# 505153_1_1.net
KiCad netlist of a schematic drawn in Altium Designer
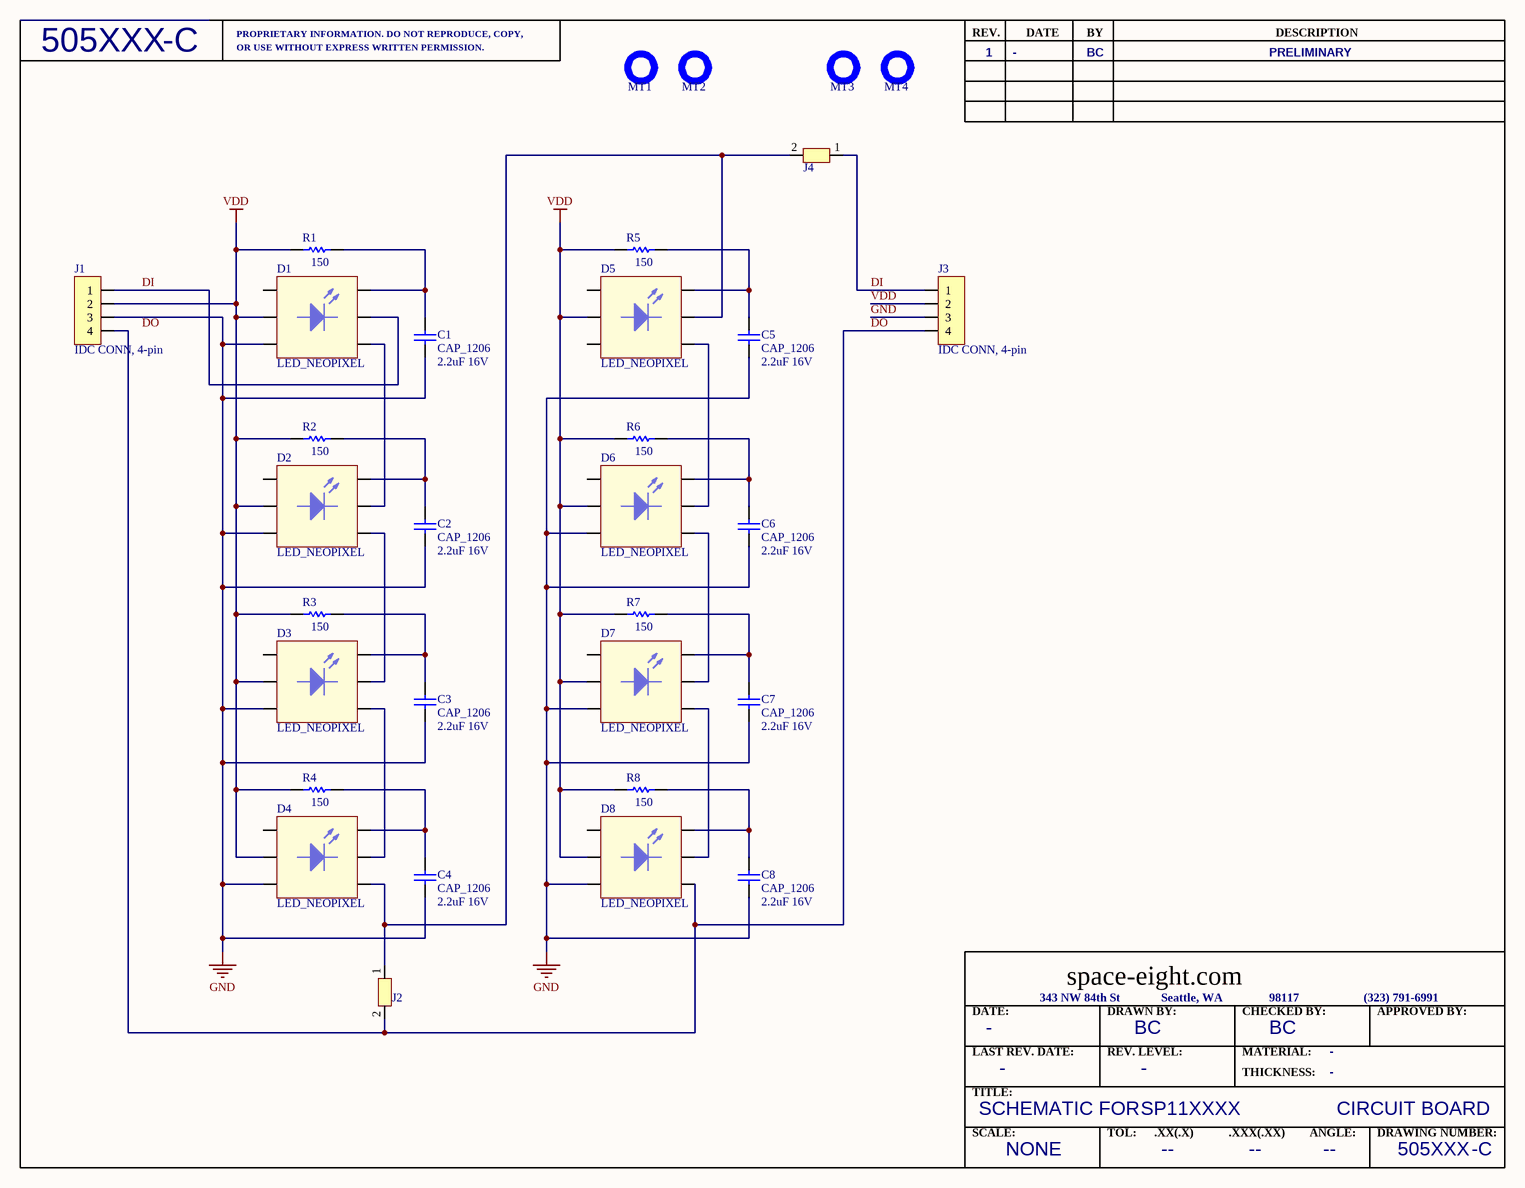
[diagram p0: 505153_1_1.SchDoc]

(export (version "E")
  (design (tool "Eeschema 10.0.6"))
  (components
    (comp (ref "C1")
      (value "CAP_1206")
      (footprint "SMT_1206_MOD")
      (description "CAP")
      (fields
        (field (name "MANUFACTURER") "Generic Components")
        (field (name "ALTIUM_VALUE") "2.2uF 16V")
        (field (name "PUBLISHER") "Altium Limited")
      )
      (libsource (lib "Custom_Lib_2") (part "CAP_1206"))
    )
    (comp (ref "C2")
      (value "CAP_1206")
      (footprint "SMT_1206_MOD")
      (description "CAP")
      (fields
        (field (name "MANUFACTURER") "Generic Components")
        (field (name "ALTIUM_VALUE") "2.2uF 16V")
        (field (name "PUBLISHER") "Altium Limited")
      )
      (libsource (lib "Custom_Lib_2") (part "CAP_1206"))
    )
    (comp (ref "C3")
      (value "CAP_1206")
      (footprint "SMT_1206_MOD")
      (description "CAP")
      (fields
        (field (name "MANUFACTURER") "Generic Components")
        (field (name "ALTIUM_VALUE") "2.2uF 16V")
        (field (name "PUBLISHER") "Altium Limited")
      )
      (libsource (lib "Custom_Lib_2") (part "CAP_1206"))
    )
    (comp (ref "C4")
      (value "CAP_1206")
      (footprint "SMT_1206_MOD")
      (description "CAP")
      (fields
        (field (name "MANUFACTURER") "Generic Components")
        (field (name "ALTIUM_VALUE") "2.2uF 16V")
        (field (name "PUBLISHER") "Altium Limited")
      )
      (libsource (lib "Custom_Lib_2") (part "CAP_1206"))
    )
    (comp (ref "C5")
      (value "CAP_1206")
      (footprint "SMT_1206_MOD")
      (description "CAP")
      (fields
        (field (name "MANUFACTURER") "Generic Components")
        (field (name "ALTIUM_VALUE") "2.2uF 16V")
        (field (name "PUBLISHER") "Altium Limited")
      )
      (libsource (lib "Custom_Lib_2") (part "CAP_1206"))
    )
    (comp (ref "C6")
      (value "CAP_1206")
      (footprint "SMT_1206_MOD")
      (description "CAP")
      (fields
        (field (name "MANUFACTURER") "Generic Components")
        (field (name "ALTIUM_VALUE") "2.2uF 16V")
        (field (name "PUBLISHER") "Altium Limited")
      )
      (libsource (lib "Custom_Lib_2") (part "CAP_1206"))
    )
    (comp (ref "C7")
      (value "CAP_1206")
      (footprint "SMT_1206_MOD")
      (description "CAP")
      (fields
        (field (name "MANUFACTURER") "Generic Components")
        (field (name "ALTIUM_VALUE") "2.2uF 16V")
        (field (name "PUBLISHER") "Altium Limited")
      )
      (libsource (lib "Custom_Lib_2") (part "CAP_1206"))
    )
    (comp (ref "C8")
      (value "CAP_1206")
      (footprint "SMT_1206_MOD")
      (description "CAP")
      (fields
        (field (name "MANUFACTURER") "Generic Components")
        (field (name "ALTIUM_VALUE") "2.2uF 16V")
        (field (name "PUBLISHER") "Altium Limited")
      )
      (libsource (lib "Custom_Lib_2") (part "CAP_1206"))
    )
    (comp (ref "D1")
      (value "LED_NEOPIXEL")
      (footprint "NEOPIXEL")
      (description "RGB NEOPIXEL")
      (fields (field (name "MANUFACTURER") "Generic Components") (field (name "PUBLISHER") "Altium Limited"))
      (libsource (lib "Custom_Lib_2") (part "LED_NEOPIXEL"))
    )
    (comp (ref "D2")
      (value "LED_NEOPIXEL")
      (footprint "NEOPIXEL")
      (description "RGB NEOPIXEL")
      (fields (field (name "MANUFACTURER") "Generic Components") (field (name "PUBLISHER") "Altium Limited"))
      (libsource (lib "Custom_Lib_2") (part "LED_NEOPIXEL"))
    )
    (comp (ref "D3")
      (value "LED_NEOPIXEL")
      (footprint "NEOPIXEL")
      (description "RGB NEOPIXEL")
      (fields (field (name "MANUFACTURER") "Generic Components") (field (name "PUBLISHER") "Altium Limited"))
      (libsource (lib "Custom_Lib_2") (part "LED_NEOPIXEL"))
    )
    (comp (ref "D4")
      (value "LED_NEOPIXEL")
      (footprint "NEOPIXEL")
      (description "RGB NEOPIXEL")
      (fields (field (name "MANUFACTURER") "Generic Components") (field (name "PUBLISHER") "Altium Limited"))
      (libsource (lib "Custom_Lib_2") (part "LED_NEOPIXEL"))
    )
    (comp (ref "D5")
      (value "LED_NEOPIXEL")
      (footprint "NEOPIXEL")
      (description "RGB NEOPIXEL")
      (fields (field (name "MANUFACTURER") "Generic Components") (field (name "PUBLISHER") "Altium Limited"))
      (libsource (lib "Custom_Lib_2") (part "LED_NEOPIXEL"))
    )
    (comp (ref "D6")
      (value "LED_NEOPIXEL")
      (footprint "NEOPIXEL")
      (description "RGB NEOPIXEL")
      (fields (field (name "MANUFACTURER") "Generic Components") (field (name "PUBLISHER") "Altium Limited"))
      (libsource (lib "Custom_Lib_2") (part "LED_NEOPIXEL"))
    )
    (comp (ref "D7")
      (value "LED_NEOPIXEL")
      (footprint "NEOPIXEL")
      (description "RGB NEOPIXEL")
      (fields (field (name "MANUFACTURER") "Generic Components") (field (name "PUBLISHER") "Altium Limited"))
      (libsource (lib "Custom_Lib_2") (part "LED_NEOPIXEL"))
    )
    (comp (ref "D8")
      (value "LED_NEOPIXEL")
      (footprint "NEOPIXEL")
      (description "RGB NEOPIXEL")
      (fields (field (name "MANUFACTURER") "Generic Components") (field (name "PUBLISHER") "Altium Limited"))
      (libsource (lib "Custom_Lib_2") (part "LED_NEOPIXEL"))
    )
    (comp (ref "J1")
      (value "IDC CONN, 4-pin")
      (footprint "IDC_CONN_SMT_4-PIN")
      (description "ICD Connector, 4-Pin")
      (fields (field (name "PUBLISHER") "Altium Limited"))
      (libsource (lib "") (part "IDC CONN, 4-pin_1"))
    )
    (comp (ref "J2") (value "JUMPER_MOD") (footprint "JUMPER_SMT") (libsource (lib "") (part "JUMPER_MOD_1")))
    (comp (ref "J3")
      (value "IDC CONN, 4-pin")
      (footprint "IDC_CONN_SMT_4-PIN")
      (description "ICD Connector, 4-Pin")
      (fields (field (name "PUBLISHER") "Altium Limited"))
      (libsource (lib "Custom_Lib_2") (part "IDC CONN, 4-pin"))
    )
    (comp (ref "J4")
      (value "JUMPER_MOD")
      (footprint "JUMPER_SMT")
      (libsource (lib "Custom_Lib_2") (part "JUMPER_MOD"))
    )
    (comp (ref "MT1")
      (value "MOUNTING HOLE")
      (footprint "MOUNTING HOLE")
      (libsource (lib "Custom_Lib_2") (part "MOUNTING HOLE"))
    )
    (comp (ref "MT2")
      (value "MOUNTING HOLE")
      (footprint "MOUNTING HOLE")
      (libsource (lib "Custom_Lib_2") (part "MOUNTING HOLE"))
    )
    (comp (ref "MT3")
      (value "MOUNTING HOLE")
      (footprint "MOUNTING HOLE")
      (libsource (lib "Custom_Lib_2") (part "MOUNTING HOLE"))
    )
    (comp (ref "MT4")
      (value "MOUNTING HOLE")
      (footprint "MOUNTING HOLE")
      (libsource (lib "Custom_Lib_2") (part "MOUNTING HOLE"))
    )
    (comp (ref "R1")
      (value "150")
      (footprint "SMT_1206_MOD")
      (description "RES")
      (fields
        (field (name "MANUFACTURER") "Generic Components")
        (field (name "Comment") "RES_1206")
        (field (name "PUBLISHER") "Altium Limited")
      )
      (libsource (lib "Custom_Lib_2") (part "RES_1206"))
    )
    (comp (ref "R2")
      (value "150")
      (footprint "SMT_1206_MOD")
      (description "RES")
      (fields
        (field (name "MANUFACTURER") "Generic Components")
        (field (name "Comment") "RES_1206")
        (field (name "PUBLISHER") "Altium Limited")
      )
      (libsource (lib "Custom_Lib_2") (part "RES_1206"))
    )
    (comp (ref "R3")
      (value "150")
      (footprint "SMT_1206_MOD")
      (description "RES")
      (fields
        (field (name "MANUFACTURER") "Generic Components")
        (field (name "Comment") "RES_1206")
        (field (name "PUBLISHER") "Altium Limited")
      )
      (libsource (lib "Custom_Lib_2") (part "RES_1206"))
    )
    (comp (ref "R4")
      (value "150")
      (footprint "SMT_1206_MOD")
      (description "RES")
      (fields
        (field (name "MANUFACTURER") "Generic Components")
        (field (name "Comment") "RES_1206")
        (field (name "PUBLISHER") "Altium Limited")
      )
      (libsource (lib "Custom_Lib_2") (part "RES_1206"))
    )
    (comp (ref "R5")
      (value "150")
      (footprint "SMT_1206_MOD")
      (description "RES")
      (fields
        (field (name "MANUFACTURER") "Generic Components")
        (field (name "Comment") "RES_1206")
        (field (name "PUBLISHER") "Altium Limited")
      )
      (libsource (lib "Custom_Lib_2") (part "RES_1206"))
    )
    (comp (ref "R6")
      (value "150")
      (footprint "SMT_1206_MOD")
      (description "RES")
      (fields
        (field (name "MANUFACTURER") "Generic Components")
        (field (name "Comment") "RES_1206")
        (field (name "PUBLISHER") "Altium Limited")
      )
      (libsource (lib "Custom_Lib_2") (part "RES_1206"))
    )
    (comp (ref "R7")
      (value "150")
      (footprint "SMT_1206_MOD")
      (description "RES")
      (fields
        (field (name "MANUFACTURER") "Generic Components")
        (field (name "Comment") "RES_1206")
        (field (name "PUBLISHER") "Altium Limited")
      )
      (libsource (lib "Custom_Lib_2") (part "RES_1206"))
    )
    (comp (ref "R8")
      (value "150")
      (footprint "SMT_1206_MOD")
      (description "RES")
      (fields
        (field (name "MANUFACTURER") "Generic Components")
        (field (name "Comment") "RES_1206")
        (field (name "PUBLISHER") "Altium Limited")
      )
      (libsource (lib "Custom_Lib_2") (part "RES_1206"))
    )
  )
  (nets
    (net (code "1") (name "/DI") (class "Default")
      (node (ref "D1") (pin "2") (pinfunction "DI_2") (pintype "passive"))
      (node (ref "J1") (pin "1") (pinfunction "1_1") (pintype "passive"))
      (node (ref "J3") (pin "1") (pinfunction "1_1") (pintype "passive"))
      (node (ref "J4") (pin "1") (pinfunction "I/_1") (pintype "passive"))
    )
    (net (code "2") (name "/DO") (class "Default")
      (node (ref "D8") (pin "1") (pinfunction "DO_1") (pintype "passive"))
      (node (ref "J1") (pin "4") (pinfunction "4_4") (pintype "passive"))
      (node (ref "J2") (pin "2") (pinfunction "O_2") (pintype "passive"))
      (node (ref "J3") (pin "4") (pinfunction "4_4") (pintype "passive"))
    )
    (net (code "3") (name "GND") (class "Default")
      (node (ref "C1") (pin "1") (pinfunction "1_1") (pintype "passive"))
      (node (ref "C2") (pin "1") (pinfunction "1_1") (pintype "passive"))
      (node (ref "C3") (pin "1") (pinfunction "1_1") (pintype "passive"))
      (node (ref "C4") (pin "1") (pinfunction "1_1") (pintype "passive"))
      (node (ref "C5") (pin "1") (pinfunction "1_1") (pintype "passive"))
      (node (ref "C6") (pin "1") (pinfunction "1_1") (pintype "passive"))
      (node (ref "C7") (pin "1") (pinfunction "1_1") (pintype "passive"))
      (node (ref "C8") (pin "1") (pinfunction "1_1") (pintype "passive"))
      (node (ref "D1") (pin "6") (pinfunction "VSS_6") (pintype "passive"))
      (node (ref "D2") (pin "6") (pinfunction "VSS_6") (pintype "passive"))
      (node (ref "D3") (pin "6") (pinfunction "VSS_6") (pintype "passive"))
      (node (ref "D4") (pin "6") (pinfunction "VSS_6") (pintype "passive"))
      (node (ref "D6") (pin "6") (pinfunction "VSS_6") (pintype "passive"))
      (node (ref "D7") (pin "6") (pinfunction "VSS_6") (pintype "passive"))
      (node (ref "D8") (pin "6") (pinfunction "VSS_6") (pintype "passive"))
      (node (ref "J1") (pin "3") (pinfunction "3_3") (pintype "passive"))
      (node (ref "J3") (pin "3") (pinfunction "3_3") (pintype "passive"))
    )
    (net (code "4") (name "Net-(D1-DO)") (class "Default")
      (node (ref "D1") (pin "1") (pinfunction "DO_1") (pintype "passive"))
      (node (ref "D2") (pin "2") (pinfunction "DI_2") (pintype "passive"))
    )
    (net (code "5") (name "Net-(D1-VCC)") (class "Default")
      (node (ref "C1") (pin "2") (pinfunction "2_2") (pintype "passive"))
      (node (ref "D1") (pin "3") (pinfunction "VCC_3") (pintype "passive"))
      (node (ref "R1") (pin "2") (pinfunction "2_2") (pintype "passive"))
    )
    (net (code "6") (name "Net-(D2-DO)") (class "Default")
      (node (ref "D2") (pin "1") (pinfunction "DO_1") (pintype "passive"))
      (node (ref "D3") (pin "2") (pinfunction "DI_2") (pintype "passive"))
    )
    (net (code "7") (name "Net-(D2-VCC)") (class "Default")
      (node (ref "C2") (pin "2") (pinfunction "2_2") (pintype "passive"))
      (node (ref "D2") (pin "3") (pinfunction "VCC_3") (pintype "passive"))
      (node (ref "R2") (pin "2") (pinfunction "2_2") (pintype "passive"))
    )
    (net (code "8") (name "Net-(D3-DO)") (class "Default")
      (node (ref "D3") (pin "1") (pinfunction "DO_1") (pintype "passive"))
      (node (ref "D4") (pin "2") (pinfunction "DI_2") (pintype "passive"))
    )
    (net (code "9") (name "Net-(D3-VCC)") (class "Default")
      (node (ref "C3") (pin "2") (pinfunction "2_2") (pintype "passive"))
      (node (ref "D3") (pin "3") (pinfunction "VCC_3") (pintype "passive"))
      (node (ref "R3") (pin "2") (pinfunction "2_2") (pintype "passive"))
    )
    (net (code "10") (name "Net-(D4-DO)") (class "Default")
      (node (ref "D4") (pin "1") (pinfunction "DO_1") (pintype "passive"))
      (node (ref "D5") (pin "2") (pinfunction "DI_2") (pintype "passive"))
      (node (ref "J2") (pin "1") (pinfunction "I/_1") (pintype "passive"))
      (node (ref "J4") (pin "2") (pinfunction "O_2") (pintype "passive"))
    )
    (net (code "11") (name "Net-(D4-VCC)") (class "Default")
      (node (ref "C4") (pin "2") (pinfunction "2_2") (pintype "passive"))
      (node (ref "D4") (pin "3") (pinfunction "VCC_3") (pintype "passive"))
      (node (ref "R4") (pin "2") (pinfunction "2_2") (pintype "passive"))
    )
    (net (code "12") (name "Net-(D5-DO)") (class "Default")
      (node (ref "D5") (pin "1") (pinfunction "DO_1") (pintype "passive"))
      (node (ref "D6") (pin "2") (pinfunction "DI_2") (pintype "passive"))
    )
    (net (code "13") (name "Net-(D5-VCC)") (class "Default")
      (node (ref "C5") (pin "2") (pinfunction "2_2") (pintype "passive"))
      (node (ref "D5") (pin "3") (pinfunction "VCC_3") (pintype "passive"))
      (node (ref "R5") (pin "2") (pinfunction "2_2") (pintype "passive"))
    )
    (net (code "14") (name "Net-(D6-DO)") (class "Default")
      (node (ref "D6") (pin "1") (pinfunction "DO_1") (pintype "passive"))
      (node (ref "D7") (pin "2") (pinfunction "DI_2") (pintype "passive"))
    )
    (net (code "15") (name "Net-(D6-VCC)") (class "Default")
      (node (ref "C6") (pin "2") (pinfunction "2_2") (pintype "passive"))
      (node (ref "D6") (pin "3") (pinfunction "VCC_3") (pintype "passive"))
      (node (ref "R6") (pin "2") (pinfunction "2_2") (pintype "passive"))
    )
    (net (code "16") (name "Net-(D7-DO)") (class "Default")
      (node (ref "D7") (pin "1") (pinfunction "DO_1") (pintype "passive"))
      (node (ref "D8") (pin "2") (pinfunction "DI_2") (pintype "passive"))
    )
    (net (code "17") (name "Net-(D7-VCC)") (class "Default")
      (node (ref "C7") (pin "2") (pinfunction "2_2") (pintype "passive"))
      (node (ref "D7") (pin "3") (pinfunction "VCC_3") (pintype "passive"))
      (node (ref "R7") (pin "2") (pinfunction "2_2") (pintype "passive"))
    )
    (net (code "18") (name "Net-(D8-VCC)") (class "Default")
      (node (ref "C8") (pin "2") (pinfunction "2_2") (pintype "passive"))
      (node (ref "D8") (pin "3") (pinfunction "VCC_3") (pintype "passive"))
      (node (ref "R8") (pin "2") (pinfunction "2_2") (pintype "passive"))
    )
    (net (code "19") (name "VDD") (class "Default")
      (node (ref "D1") (pin "5") (pinfunction "VDD_5") (pintype "passive"))
      (node (ref "D2") (pin "5") (pinfunction "VDD_5") (pintype "passive"))
      (node (ref "D3") (pin "5") (pinfunction "VDD_5") (pintype "passive"))
      (node (ref "D4") (pin "5") (pinfunction "VDD_5") (pintype "passive"))
      (node (ref "D5") (pin "5") (pinfunction "VDD_5") (pintype "passive"))
      (node (ref "D6") (pin "5") (pinfunction "VDD_5") (pintype "passive"))
      (node (ref "D7") (pin "5") (pinfunction "VDD_5") (pintype "passive"))
      (node (ref "D8") (pin "5") (pinfunction "VDD_5") (pintype "passive"))
      (node (ref "J1") (pin "2") (pinfunction "2_2") (pintype "passive"))
      (node (ref "J3") (pin "2") (pinfunction "2_2") (pintype "passive"))
      (node (ref "R1") (pin "1") (pinfunction "1_1") (pintype "passive"))
      (node (ref "R2") (pin "1") (pinfunction "1_1") (pintype "passive"))
      (node (ref "R3") (pin "1") (pinfunction "1_1") (pintype "passive"))
      (node (ref "R4") (pin "1") (pinfunction "1_1") (pintype "passive"))
      (node (ref "R5") (pin "1") (pinfunction "1_1") (pintype "passive"))
      (node (ref "R6") (pin "1") (pinfunction "1_1") (pintype "passive"))
      (node (ref "R7") (pin "1") (pinfunction "1_1") (pintype "passive"))
      (node (ref "R8") (pin "1") (pinfunction "1_1") (pintype "passive"))
    )
    (net (code "20") (name "unconnected-(D1-NC-Pad4)") (class "Default")
      (node (ref "D1") (pin "4") (pinfunction "NC_4") (pintype "passive"))
    )
    (net (code "21") (name "unconnected-(D2-NC-Pad4)") (class "Default")
      (node (ref "D2") (pin "4") (pinfunction "NC_4") (pintype "passive"))
    )
    (net (code "22") (name "unconnected-(D3-NC-Pad4)") (class "Default")
      (node (ref "D3") (pin "4") (pinfunction "NC_4") (pintype "passive"))
    )
    (net (code "23") (name "unconnected-(D4-NC-Pad4)") (class "Default")
      (node (ref "D4") (pin "4") (pinfunction "NC_4") (pintype "passive"))
    )
    (net (code "24") (name "unconnected-(D5-NC-Pad4)") (class "Default")
      (node (ref "D5") (pin "4") (pinfunction "NC_4") (pintype "passive"))
    )
    (net (code "25") (name "unconnected-(D5-VSS-Pad6)") (class "Default")
      (node (ref "D5") (pin "6") (pinfunction "VSS_6") (pintype "passive"))
    )
    (net (code "26") (name "unconnected-(D6-NC-Pad4)") (class "Default")
      (node (ref "D6") (pin "4") (pinfunction "NC_4") (pintype "passive"))
    )
    (net (code "27") (name "unconnected-(D7-NC-Pad4)") (class "Default")
      (node (ref "D7") (pin "4") (pinfunction "NC_4") (pintype "passive"))
    )
    (net (code "28") (name "unconnected-(D8-NC-Pad4)") (class "Default")
      (node (ref "D8") (pin "4") (pinfunction "NC_4") (pintype "passive"))
    )
  )
)
